# CHAIRI2CXIAO.net
KiCad netlist of a schematic drawn in EAGLE
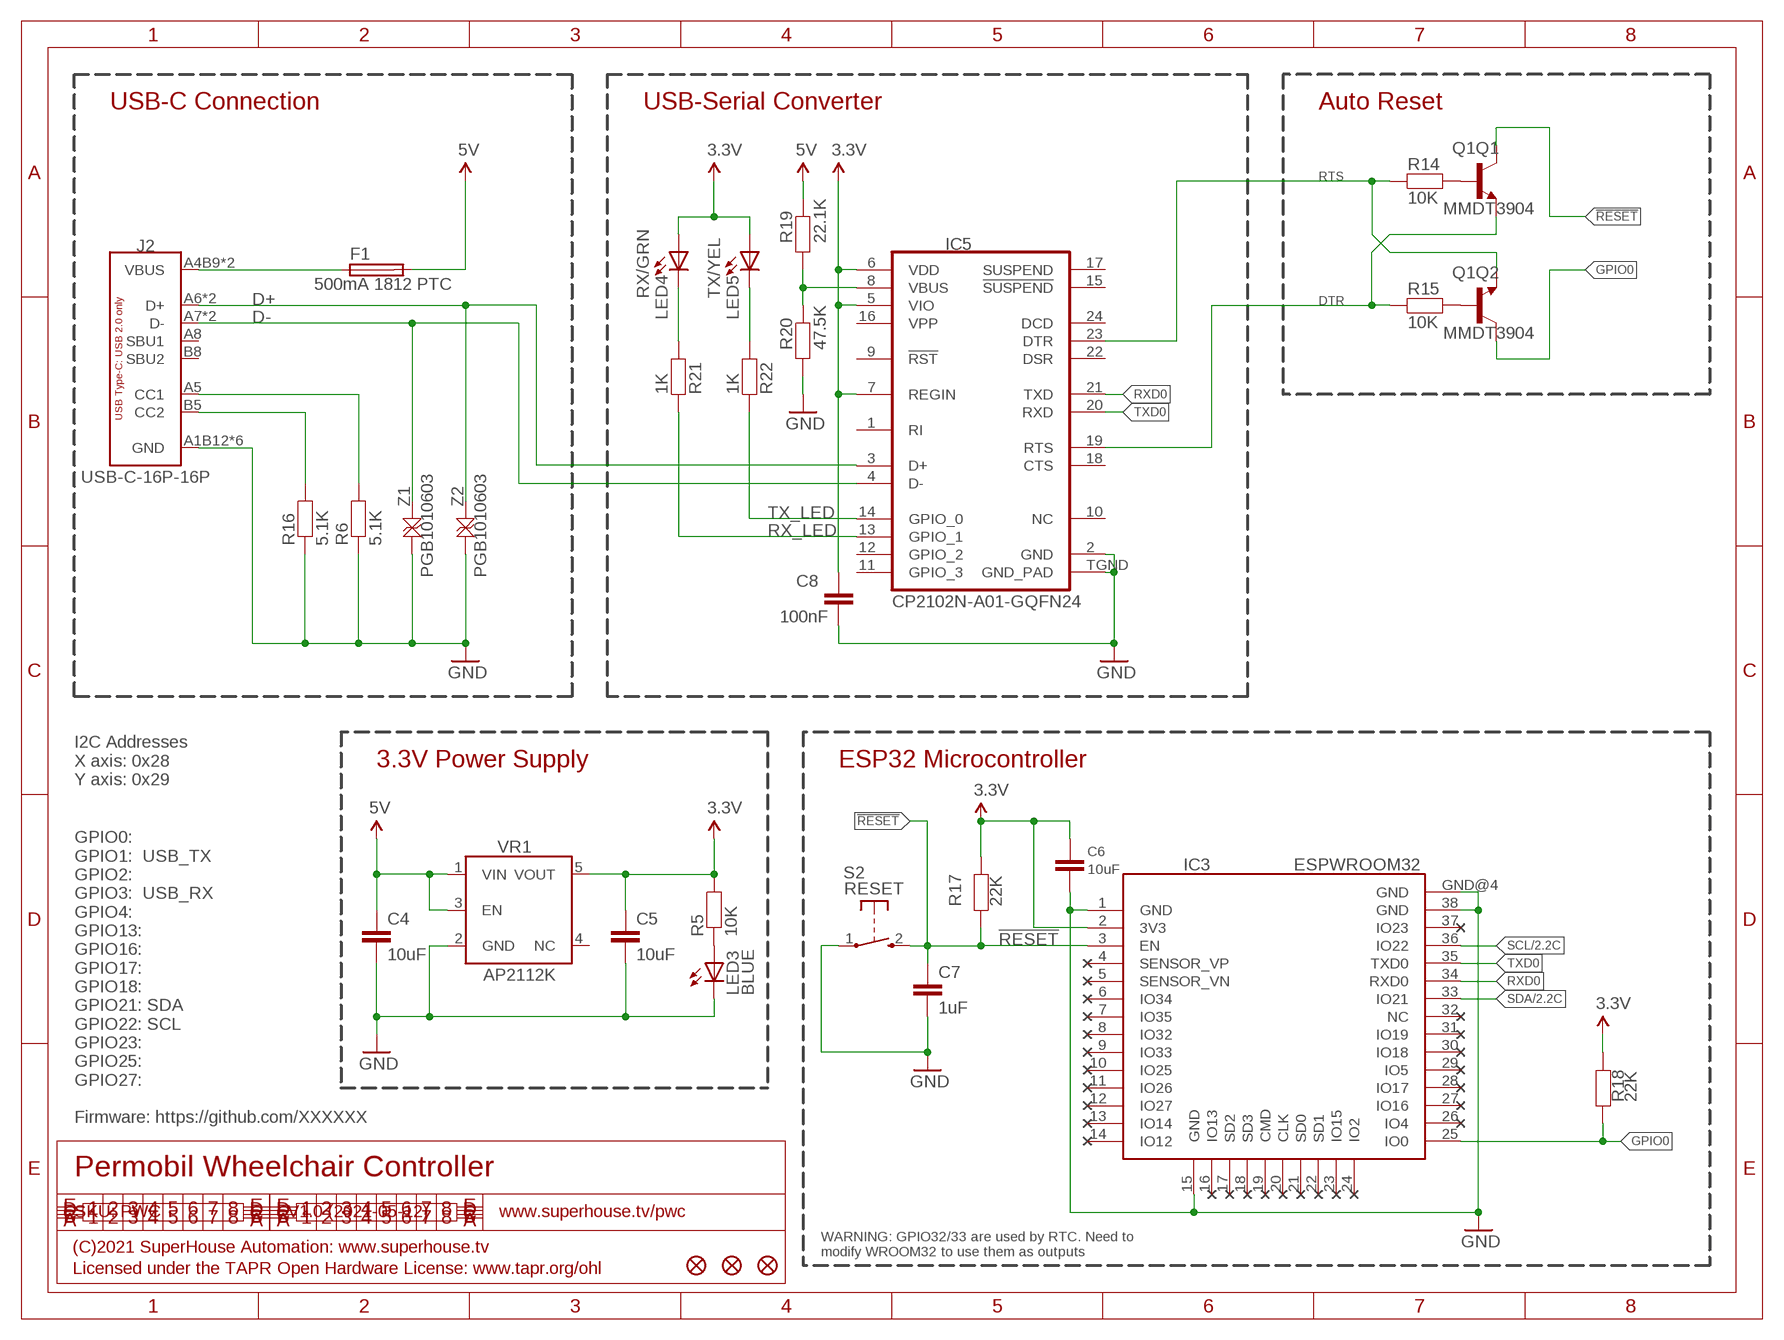
[diagram p0: schematic, sheet 1]
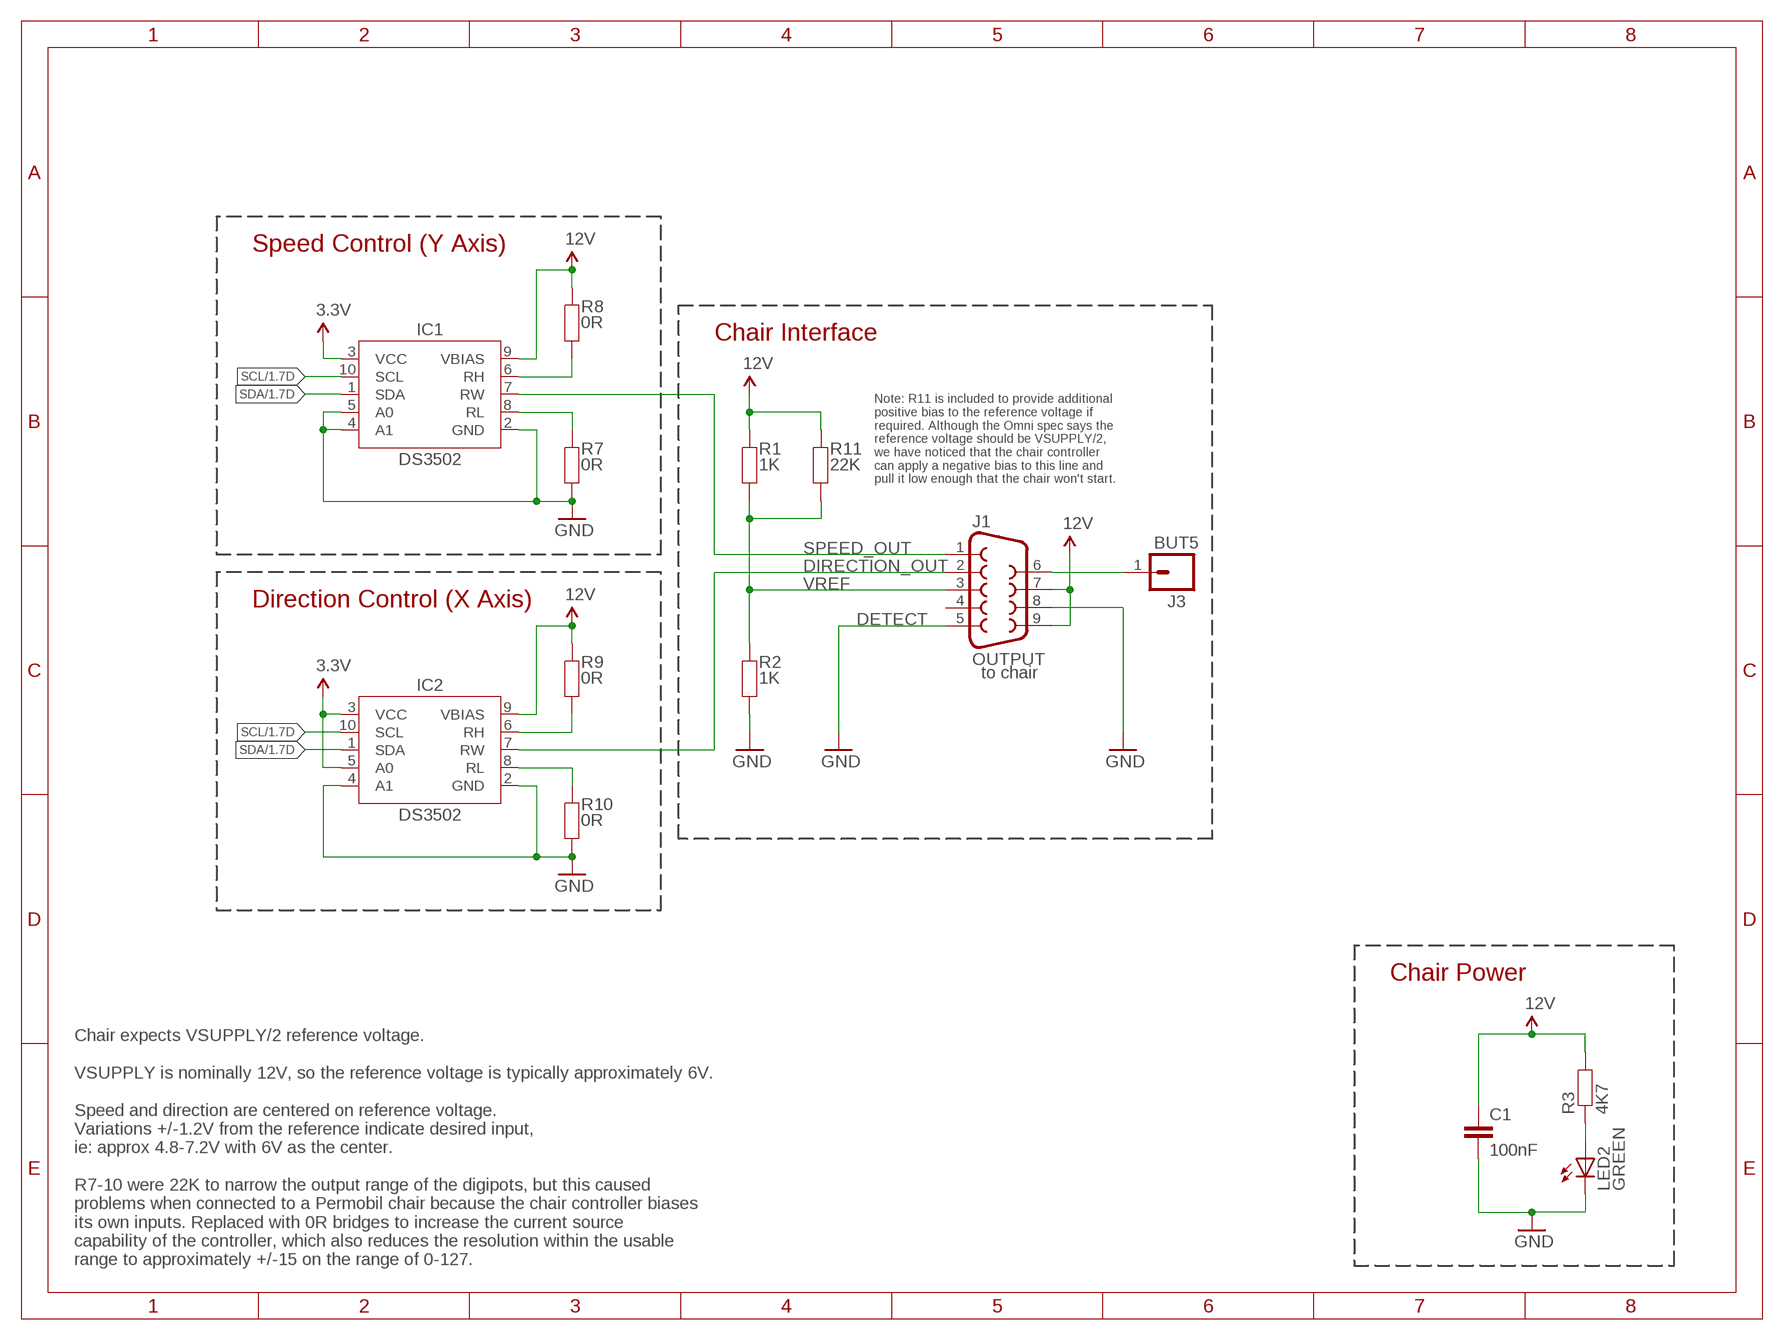
[diagram p1: schematic, sheet 2]

(export (version "E")
  (design (tool "Eeschema 10.0.6"))
  (components
    (comp (ref "C1")
      (value "100nF")
      (footprint "eagle-import:C0603")
      (libsource (lib "eagle-import") (part "CAP0603"))
    )
    (comp (ref "IC1")
      (value "DS3502")
      (footprint "eagle-import:MSOP10")
      (libsource (lib "eagle-import") (part "DS3502"))
    )
    (comp (ref "IC2")
      (value "DS3502")
      (footprint "eagle-import:MSOP10")
      (libsource (lib "eagle-import") (part "DS3502"))
    )
    (comp (ref "J1")
      (value "OUTPUT")
      (footprint "eagle-import:DB9-PCB-SOCKET")
      (libsource (lib "eagle-import") (part "DB9-PCB-SOCKET"))
    )
    (comp (ref "J3")
      (value "BUT5")
      (footprint "eagle-import:1X01")
      (libsource (lib "eagle-import") (part "M01-PLAIN"))
    )
    (comp (ref "LED2")
      (value "GREEN")
      (footprint "eagle-import:LED-0603")
      (libsource (lib "eagle-import") (part "LED0603"))
    )
    (comp (ref "R1")
      (value "1K")
      (footprint "eagle-import:R0603")
      (libsource (lib "eagle-import") (part "RESISTOR0603"))
    )
    (comp (ref "R2")
      (value "1K")
      (footprint "eagle-import:R0603")
      (libsource (lib "eagle-import") (part "RESISTOR0603"))
    )
    (comp (ref "R3")
      (value "4K7")
      (footprint "eagle-import:R0603")
      (libsource (lib "eagle-import") (part "RESISTOR0603"))
    )
    (comp (ref "R7")
      (value "0R")
      (footprint "eagle-import:R0603")
      (libsource (lib "eagle-import") (part "RESISTOR0603"))
    )
    (comp (ref "R8")
      (value "0R")
      (footprint "eagle-import:R0603")
      (libsource (lib "eagle-import") (part "RESISTOR0603"))
    )
    (comp (ref "R9")
      (value "0R")
      (footprint "eagle-import:R0603")
      (libsource (lib "eagle-import") (part "RESISTOR0603"))
    )
    (comp (ref "R10")
      (value "0R")
      (footprint "eagle-import:R0603")
      (libsource (lib "eagle-import") (part "RESISTOR0603"))
    )
    (comp (ref "R11")
      (value "22K")
      (footprint "eagle-import:R0603")
      (libsource (lib "eagle-import") (part "RESISTOR0603"))
    )
    (comp (ref "C4")
      (value "10uF")
      (footprint "eagle-import:C0805")
      (libsource (lib "eagle-import") (part "CAP0805"))
    )
    (comp (ref "C5")
      (value "10uF")
      (footprint "eagle-import:C0805")
      (libsource (lib "eagle-import") (part "CAP0805"))
    )
    (comp (ref "C6")
      (value "10uF")
      (footprint "eagle-import:C0805")
      (libsource (lib "eagle-import") (part "CAP0805"))
    )
    (comp (ref "C7")
      (value "1uF")
      (footprint "eagle-import:C0603")
      (libsource (lib "eagle-import") (part "CAP0603"))
    )
    (comp (ref "C8")
      (value "100nF")
      (footprint "eagle-import:C0603")
      (libsource (lib "eagle-import") (part "CAP0603"))
    )
    (comp (ref "F1")
      (value "500mA 1812 PTC")
      (footprint "eagle-import:1812")
      (libsource (lib "eagle-import") (part "PTC050"))
    )
    (comp (ref "IC3")
      (value "ESPWROOM32")
      (footprint "eagle-import:ESPWROOM32")
      (libsource (lib "eagle-import") (part "ESPWROOM32"))
    )
    (comp (ref "IC5")
      (value "CP2102N-A01-GQFN24")
      (footprint "eagle-import:QFN-24")
      (libsource (lib "eagle-import") (part "CP2104"))
    )
    (comp (ref "J2")
      (value "USB-C-16P-16P")
      (footprint "eagle-import:USB-C-16P")
      (libsource (lib "eagle-import") (part "USB-C-16P-16P"))
    )
    (comp (ref "LED3")
      (value "BLUE")
      (footprint "eagle-import:LED-0603")
      (libsource (lib "eagle-import") (part "LED0603"))
    )
    (comp (ref "LED4")
      (value "RX/GRN")
      (footprint "eagle-import:LED-0603")
      (libsource (lib "eagle-import") (part "LED0603"))
    )
    (comp (ref "LED5")
      (value "TX/YEL")
      (footprint "eagle-import:LED-0603")
      (libsource (lib "eagle-import") (part "LED0603"))
    )
    (comp (ref "Q1")
      (value "MMDT3904")
      (footprint "eagle-import:SOT-363")
      (libsource (lib "eagle-import") (part "TRANS_NPN_DUAL-MMDT3904"))
    )
    (comp (ref "R5")
      (value "10K")
      (footprint "eagle-import:R0603")
      (libsource (lib "eagle-import") (part "RESISTOR0603"))
    )
    (comp (ref "R6")
      (value "5.1K")
      (footprint "eagle-import:R0603")
      (libsource (lib "eagle-import") (part "RESISTOR0603"))
    )
    (comp (ref "R14")
      (value "10K")
      (footprint "eagle-import:R0603")
      (libsource (lib "eagle-import") (part "RESISTOR0603"))
    )
    (comp (ref "R15")
      (value "10K")
      (footprint "eagle-import:R0603")
      (libsource (lib "eagle-import") (part "RESISTOR0603"))
    )
    (comp (ref "R16")
      (value "5.1K")
      (footprint "eagle-import:R0603")
      (libsource (lib "eagle-import") (part "RESISTOR0603"))
    )
    (comp (ref "R17")
      (value "22K")
      (footprint "eagle-import:R0603")
      (libsource (lib "eagle-import") (part "RESISTOR0603"))
    )
    (comp (ref "R18")
      (value "22K")
      (footprint "eagle-import:R0603")
      (libsource (lib "eagle-import") (part "RESISTOR0603"))
    )
    (comp (ref "R19")
      (value "22.1K")
      (footprint "eagle-import:R0603")
      (libsource (lib "eagle-import") (part "RESISTOR0603"))
    )
    (comp (ref "R20")
      (value "47.5K")
      (footprint "eagle-import:R0603")
      (libsource (lib "eagle-import") (part "RESISTOR0603"))
    )
    (comp (ref "R21")
      (value "1K")
      (footprint "eagle-import:R0603")
      (libsource (lib "eagle-import") (part "RESISTOR0603"))
    )
    (comp (ref "R22")
      (value "1K")
      (footprint "eagle-import:R0603")
      (libsource (lib "eagle-import") (part "RESISTOR0603"))
    )
    (comp (ref "S2")
      (value "RESET")
      (footprint "eagle-import:TACTILE_SMT_3X4X2")
      (libsource (lib "eagle-import") (part "TAC_SWITCH_2PINSMT"))
    )
    (comp (ref "U$35")
      (value "FIDUCIAL1X2")
      (footprint "eagle-import:FIDUCIAL-1X2")
      (libsource (lib "eagle-import") (part "FIDUCIAL1X2"))
    )
    (comp (ref "U$36")
      (value "FIDUCIAL1X2")
      (footprint "eagle-import:FIDUCIAL-1X2")
      (libsource (lib "eagle-import") (part "FIDUCIAL1X2"))
    )
    (comp (ref "U$37")
      (value "FIDUCIAL1X2")
      (footprint "eagle-import:FIDUCIAL-1X2")
      (libsource (lib "eagle-import") (part "FIDUCIAL1X2"))
    )
    (comp (ref "VR1")
      (value "AP2112KSOT25")
      (footprint "eagle-import:SOT23-5")
      (libsource (lib "eagle-import") (part "AP2112KSOT25"))
    )
    (comp (ref "Z1")
      (value "PGB1010603")
      (footprint "eagle-import:TVS0603")
      (libsource (lib "eagle-import") (part "TVS0603"))
    )
    (comp (ref "Z2")
      (value "PGB1010603")
      (footprint "eagle-import:TVS0603")
      (libsource (lib "eagle-import") (part "TVS0603"))
    )
  )
  (nets
    (net (code "1") (name "3.3V") (class "Default")
      (node (ref "C5") (pin "1") (pinfunction "1_1") (pintype "passive"))
      (node (ref "C6") (pin "1") (pinfunction "1_1") (pintype "passive"))
      (node (ref "C8") (pin "1") (pinfunction "1_1") (pintype "passive"))
      (node (ref "IC1") (pin "3") (pinfunction "VCC_3") (pintype "power_in"))
      (node (ref "IC2") (pin "3") (pinfunction "VCC_3") (pintype "power_in"))
      (node (ref "IC2") (pin "5") (pinfunction "A0_5") (pintype "input"))
      (node (ref "IC3") (pin "2") (pinfunction "3V3_2") (pintype "power_in"))
      (node (ref "IC5") (pin "5") (pinfunction "VIO_5") (pintype "bidirectional"))
      (node (ref "IC5") (pin "6") (pinfunction "VDD_6") (pintype "power_in"))
      (node (ref "IC5") (pin "7") (pinfunction "REGIN_7") (pintype "power_in"))
      (node (ref "LED4") (pin "A") (pinfunction "A_A") (pintype "passive"))
      (node (ref "LED5") (pin "A") (pinfunction "A_A") (pintype "passive"))
      (node (ref "R17") (pin "1") (pinfunction "1_1") (pintype "passive"))
      (node (ref "R18") (pin "1") (pinfunction "1_1") (pintype "passive"))
      (node (ref "R5") (pin "2") (pinfunction "2_2") (pintype "passive"))
      (node (ref "VR1") (pin "5") (pinfunction "VOUT_5") (pintype "bidirectional"))
    )
    (net (code "2") (name "5V") (class "Default")
      (node (ref "C4") (pin "1") (pinfunction "1_1") (pintype "passive"))
      (node (ref "F1") (pin "2") (pinfunction "2_2") (pintype "passive"))
      (node (ref "R19") (pin "2") (pinfunction "2_2") (pintype "passive"))
      (node (ref "VR1") (pin "1") (pinfunction "VIN_1") (pintype "bidirectional"))
      (node (ref "VR1") (pin "3") (pinfunction "EN_3") (pintype "bidirectional"))
    )
    (net (code "3") (name "12V") (class "Default")
      (node (ref "C1") (pin "1") (pinfunction "1_1") (pintype "passive"))
      (node (ref "IC1") (pin "9") (pinfunction "VBIAS_9") (pintype "power_in"))
      (node (ref "IC2") (pin "9") (pinfunction "VBIAS_9") (pintype "power_in"))
      (node (ref "J1") (pin "7") (pinfunction "7_7") (pintype "passive"))
      (node (ref "J1") (pin "9") (pinfunction "9_9") (pintype "passive"))
      (node (ref "R1") (pin "2") (pinfunction "2_2") (pintype "passive"))
      (node (ref "R11") (pin "2") (pinfunction "2_2") (pintype "passive"))
      (node (ref "R3") (pin "2") (pinfunction "2_2") (pintype "passive"))
      (node (ref "R8") (pin "2") (pinfunction "2_2") (pintype "passive"))
      (node (ref "R9") (pin "2") (pinfunction "2_2") (pintype "passive"))
    )
    (net (code "4") (name "D+") (class "Default")
      (node (ref "IC5") (pin "3") (pinfunction "D+_3") (pintype "bidirectional"))
      (node (ref "J2") (pin "A6") (pinfunction "D+_A6") (pintype "bidirectional"))
      (node (ref "J2") (pin "B6") (pinfunction "D+_B6") (pintype "bidirectional"))
      (node (ref "Z2") (pin "2") (pinfunction "2_2") (pintype "passive"))
    )
    (net (code "5") (name "D-") (class "Default")
      (node (ref "IC5") (pin "4") (pinfunction "D-_4") (pintype "bidirectional"))
      (node (ref "J2") (pin "A7") (pinfunction "D-_A7") (pintype "bidirectional"))
      (node (ref "J2") (pin "B7") (pinfunction "D-_B7") (pintype "bidirectional"))
      (node (ref "Z1") (pin "2") (pinfunction "2_2") (pintype "passive"))
    )
    (net (code "6") (name "DIRECTION_OUT") (class "Default")
      (node (ref "IC2") (pin "7") (pinfunction "RW_7") (pintype "passive"))
      (node (ref "J1") (pin "2") (pinfunction "2_2") (pintype "passive"))
    )
    (net (code "7") (name "DTR") (class "Default")
      (node (ref "IC5") (pin "23") (pinfunction "DTR_23") (pintype "output"))
      (node (ref "Q1") (pin "1") (pinfunction "E_1") (pintype "passive"))
      (node (ref "R14") (pin "1") (pinfunction "1_1") (pintype "passive"))
    )
    (net (code "8") (name "GND") (class "Default")
      (node (ref "C1") (pin "2") (pinfunction "2_2") (pintype "passive"))
      (node (ref "C4") (pin "2") (pinfunction "2_2") (pintype "passive"))
      (node (ref "C5") (pin "2") (pinfunction "2_2") (pintype "passive"))
      (node (ref "C6") (pin "2") (pinfunction "2_2") (pintype "passive"))
      (node (ref "C7") (pin "2") (pinfunction "2_2") (pintype "passive"))
      (node (ref "C8") (pin "2") (pinfunction "2_2") (pintype "passive"))
      (node (ref "IC1") (pin "2") (pinfunction "GND_2") (pintype "power_in"))
      (node (ref "IC1") (pin "4") (pinfunction "A1_4") (pintype "input"))
      (node (ref "IC1") (pin "5") (pinfunction "A0_5") (pintype "input"))
      (node (ref "IC2") (pin "2") (pinfunction "GND_2") (pintype "power_in"))
      (node (ref "IC2") (pin "4") (pinfunction "A1_4") (pintype "input"))
      (node (ref "IC3") (pin "1") (pinfunction "GND_1") (pintype "power_in"))
      (node (ref "IC3") (pin "15") (pinfunction "GND_15") (pintype "power_in"))
      (node (ref "IC3") (pin "38") (pinfunction "GND_38") (pintype "power_in"))
      (node (ref "IC3") (pin "GND@4") (pinfunction "GND_GND@4") (pintype "power_in"))
      (node (ref "IC5") (pin "2") (pinfunction "GND_2") (pintype "power_in"))
      (node (ref "IC5") (pin "TGND") (pinfunction "GND_PAD_TGND") (pintype "power_in"))
      (node (ref "J1") (pin "5") (pinfunction "5_5") (pintype "passive"))
      (node (ref "J1") (pin "8") (pinfunction "8_8") (pintype "passive"))
      (node (ref "J2") (pin "A12B1") (pinfunction "GND_A12B1") (pintype "power_in"))
      (node (ref "J2") (pin "A1B12") (pinfunction "GND_A1B12") (pintype "power_in"))
      (node (ref "J2") (pin "FIX1") (pinfunction "GND_FIX1") (pintype "power_in"))
      (node (ref "J2") (pin "FIX2") (pinfunction "GND_FIX2") (pintype "power_in"))
      (node (ref "J2") (pin "FIX3") (pinfunction "GND_FIX3") (pintype "power_in"))
      (node (ref "J2") (pin "FIX4") (pinfunction "GND_FIX4") (pintype "power_in"))
      (node (ref "LED2") (pin "C") (pinfunction "C_C") (pintype "passive"))
      (node (ref "LED3") (pin "C") (pinfunction "C_C") (pintype "passive"))
      (node (ref "R10") (pin "1") (pinfunction "1_1") (pintype "passive"))
      (node (ref "R16") (pin "1") (pinfunction "1_1") (pintype "passive"))
      (node (ref "R2") (pin "1") (pinfunction "1_1") (pintype "passive"))
      (node (ref "R20") (pin "1") (pinfunction "1_1") (pintype "passive"))
      (node (ref "R6") (pin "1") (pinfunction "1_1") (pintype "passive"))
      (node (ref "R7") (pin "1") (pinfunction "1_1") (pintype "passive"))
      (node (ref "S2") (pin "1") (pinfunction "P_1") (pintype "passive"))
      (node (ref "VR1") (pin "2") (pinfunction "GND_2") (pintype "bidirectional"))
      (node (ref "Z1") (pin "1") (pinfunction "1_1") (pintype "passive"))
      (node (ref "Z2") (pin "1") (pinfunction "1_1") (pintype "passive"))
    )
    (net (code "9") (name "GPIO0") (class "Default")
      (node (ref "IC3") (pin "25") (pinfunction "IO0_25") (pintype "bidirectional"))
      (node (ref "Q1") (pin "6") (pinfunction "C_6") (pintype "passive"))
      (node (ref "R18") (pin "2") (pinfunction "2_2") (pintype "passive"))
    )
    (net (code "10") (name "Net-(F1-Pad1)") (class "Default")
      (node (ref "F1") (pin "1") (pinfunction "1_1") (pintype "passive"))
      (node (ref "J2") (pin "A4B9") (pinfunction "VBUS_A4B9") (pintype "power_in"))
      (node (ref "J2") (pin "A9B4") (pinfunction "VBUS_A9B4") (pintype "power_in"))
    )
    (net (code "11") (name "Net-(IC1-RH)") (class "Default")
      (node (ref "IC1") (pin "6") (pinfunction "RH_6") (pintype "passive"))
      (node (ref "R8") (pin "1") (pinfunction "1_1") (pintype "passive"))
    )
    (net (code "12") (name "Net-(IC1-RL)") (class "Default")
      (node (ref "IC1") (pin "8") (pinfunction "RL_8") (pintype "passive"))
      (node (ref "R7") (pin "2") (pinfunction "2_2") (pintype "passive"))
    )
    (net (code "13") (name "Net-(IC2-RH)") (class "Default")
      (node (ref "IC2") (pin "6") (pinfunction "RH_6") (pintype "passive"))
      (node (ref "R9") (pin "1") (pinfunction "1_1") (pintype "passive"))
    )
    (net (code "14") (name "Net-(IC2-RL)") (class "Default")
      (node (ref "IC2") (pin "8") (pinfunction "RL_8") (pintype "passive"))
      (node (ref "R10") (pin "2") (pinfunction "2_2") (pintype "passive"))
    )
    (net (code "15") (name "Net-(IC5-VBUS)") (class "Default")
      (node (ref "IC5") (pin "8") (pinfunction "VBUS_8") (pintype "bidirectional"))
      (node (ref "R19") (pin "1") (pinfunction "1_1") (pintype "passive"))
      (node (ref "R20") (pin "2") (pinfunction "2_2") (pintype "passive"))
    )
    (net (code "16") (name "Net-(J1-Pad6)") (class "Default")
      (node (ref "J1") (pin "6") (pinfunction "6_6") (pintype "passive"))
      (node (ref "J3") (pin "1") (pinfunction "1_1") (pintype "passive"))
    )
    (net (code "17") (name "Net-(J2-CC1)") (class "Default")
      (node (ref "J2") (pin "A5") (pinfunction "CC1_A5") (pintype "bidirectional"))
      (node (ref "R6") (pin "2") (pinfunction "2_2") (pintype "passive"))
    )
    (net (code "18") (name "Net-(J2-CC2)") (class "Default")
      (node (ref "J2") (pin "B5") (pinfunction "CC2_B5") (pintype "bidirectional"))
      (node (ref "R16") (pin "2") (pinfunction "2_2") (pintype "passive"))
    )
    (net (code "19") (name "Net-(LED2-PadA)") (class "Default")
      (node (ref "LED2") (pin "A") (pinfunction "A_A") (pintype "passive"))
      (node (ref "R3") (pin "1") (pinfunction "1_1") (pintype "passive"))
    )
    (net (code "20") (name "Net-(LED3-PadA)") (class "Default")
      (node (ref "LED3") (pin "A") (pinfunction "A_A") (pintype "passive"))
      (node (ref "R5") (pin "1") (pinfunction "1_1") (pintype "passive"))
    )
    (net (code "21") (name "Net-(LED4-PadC)") (class "Default")
      (node (ref "LED4") (pin "C") (pinfunction "C_C") (pintype "passive"))
      (node (ref "R21") (pin "2") (pinfunction "2_2") (pintype "passive"))
    )
    (net (code "22") (name "Net-(LED5-PadC)") (class "Default")
      (node (ref "LED5") (pin "C") (pinfunction "C_C") (pintype "passive"))
      (node (ref "R22") (pin "2") (pinfunction "2_2") (pintype "passive"))
    )
    (net (code "23") (name "Net-(Q1A-B)") (class "Default")
      (node (ref "Q1") (pin "5") (pinfunction "B_5") (pintype "passive"))
      (node (ref "R14") (pin "2") (pinfunction "2_2") (pintype "passive"))
    )
    (net (code "24") (name "Net-(Q1B-B)") (class "Default")
      (node (ref "Q1") (pin "2") (pinfunction "B_2") (pintype "passive"))
      (node (ref "R15") (pin "2") (pinfunction "2_2") (pintype "passive"))
    )
    (net (code "25") (name "RTS") (class "Default")
      (node (ref "IC5") (pin "19") (pinfunction "RTS_19") (pintype "output"))
      (node (ref "Q1") (pin "4") (pinfunction "E_4") (pintype "passive"))
      (node (ref "R15") (pin "1") (pinfunction "1_1") (pintype "passive"))
    )
    (net (code "26") (name "RXD0") (class "Default")
      (node (ref "IC3") (pin "34") (pinfunction "RXD0_34") (pintype "bidirectional"))
      (node (ref "IC5") (pin "21") (pinfunction "TXD_21") (pintype "output"))
    )
    (net (code "27") (name "RX_LED") (class "Default")
      (node (ref "IC5") (pin "13") (pinfunction "GPIO_1_13") (pintype "bidirectional"))
      (node (ref "R21") (pin "1") (pinfunction "1_1") (pintype "passive"))
    )
    (net (code "28") (name "SCL") (class "Default")
      (node (ref "IC1") (pin "10") (pinfunction "SCL_10") (pintype "input"))
      (node (ref "IC2") (pin "10") (pinfunction "SCL_10") (pintype "input"))
      (node (ref "IC3") (pin "36") (pinfunction "IO22_36") (pintype "bidirectional"))
    )
    (net (code "29") (name "SDA") (class "Default")
      (node (ref "IC1") (pin "1") (pinfunction "SDA_1") (pintype "bidirectional"))
      (node (ref "IC2") (pin "1") (pinfunction "SDA_1") (pintype "bidirectional"))
      (node (ref "IC3") (pin "33") (pinfunction "IO21_33") (pintype "bidirectional"))
    )
    (net (code "30") (name "SPEED_OUT") (class "Default")
      (node (ref "IC1") (pin "7") (pinfunction "RW_7") (pintype "passive"))
      (node (ref "J1") (pin "1") (pinfunction "1_1") (pintype "passive"))
    )
    (net (code "31") (name "TXD0") (class "Default")
      (node (ref "IC3") (pin "35") (pinfunction "TXD0_35") (pintype "bidirectional"))
      (node (ref "IC5") (pin "20") (pinfunction "RXD_20") (pintype "input"))
    )
    (net (code "32") (name "TX_LED") (class "Default")
      (node (ref "IC5") (pin "14") (pinfunction "GPIO_0_14") (pintype "bidirectional"))
      (node (ref "R22") (pin "1") (pinfunction "1_1") (pintype "passive"))
    )
    (net (code "33") (name "VREF") (class "Default")
      (node (ref "J1") (pin "3") (pinfunction "3_3") (pintype "passive"))
      (node (ref "R1") (pin "1") (pinfunction "1_1") (pintype "passive"))
      (node (ref "R11") (pin "1") (pinfunction "1_1") (pintype "passive"))
      (node (ref "R2") (pin "2") (pinfunction "2_2") (pintype "passive"))
    )
    (net (code "34") (name "unconnected-(IC3-CLK-Pad20)") (class "Default")
      (node (ref "IC3") (pin "20") (pinfunction "CLK_20") (pintype "bidirectional"))
    )
    (net (code "35") (name "unconnected-(IC3-CMD-Pad19)") (class "Default")
      (node (ref "IC3") (pin "19") (pinfunction "CMD_19") (pintype "bidirectional"))
    )
    (net (code "36") (name "unconnected-(IC3-IO2-Pad24)") (class "Default")
      (node (ref "IC3") (pin "24") (pinfunction "IO2_24") (pintype "bidirectional"))
    )
    (net (code "37") (name "unconnected-(IC3-IO4-Pad26)") (class "Default")
      (node (ref "IC3") (pin "26") (pinfunction "IO4_26") (pintype "bidirectional"))
    )
    (net (code "38") (name "unconnected-(IC3-IO5-Pad29)") (class "Default")
      (node (ref "IC3") (pin "29") (pinfunction "IO5_29") (pintype "bidirectional"))
    )
    (net (code "39") (name "unconnected-(IC3-IO12-Pad14)") (class "Default")
      (node (ref "IC3") (pin "14") (pinfunction "IO12_14") (pintype "bidirectional"))
    )
    (net (code "40") (name "unconnected-(IC3-IO13-Pad16)") (class "Default")
      (node (ref "IC3") (pin "16") (pinfunction "IO13_16") (pintype "bidirectional"))
    )
    (net (code "41") (name "unconnected-(IC3-IO14-Pad13)") (class "Default")
      (node (ref "IC3") (pin "13") (pinfunction "IO14_13") (pintype "bidirectional"))
    )
    (net (code "42") (name "unconnected-(IC3-IO15-Pad23)") (class "Default")
      (node (ref "IC3") (pin "23") (pinfunction "IO15_23") (pintype "bidirectional"))
    )
    (net (code "43") (name "unconnected-(IC3-IO16-Pad27)") (class "Default")
      (node (ref "IC3") (pin "27") (pinfunction "IO16_27") (pintype "bidirectional"))
    )
    (net (code "44") (name "unconnected-(IC3-IO17-Pad28)") (class "Default")
      (node (ref "IC3") (pin "28") (pinfunction "IO17_28") (pintype "bidirectional"))
    )
    (net (code "45") (name "unconnected-(IC3-IO18-Pad30)") (class "Default")
      (node (ref "IC3") (pin "30") (pinfunction "IO18_30") (pintype "bidirectional"))
    )
    (net (code "46") (name "unconnected-(IC3-IO19-Pad31)") (class "Default")
      (node (ref "IC3") (pin "31") (pinfunction "IO19_31") (pintype "bidirectional"))
    )
    (net (code "47") (name "unconnected-(IC3-IO23-Pad37)") (class "Default")
      (node (ref "IC3") (pin "37") (pinfunction "IO23_37") (pintype "bidirectional"))
    )
    (net (code "48") (name "unconnected-(IC3-IO25-Pad10)") (class "Default")
      (node (ref "IC3") (pin "10") (pinfunction "IO25_10") (pintype "bidirectional"))
    )
    (net (code "49") (name "unconnected-(IC3-IO26-Pad11)") (class "Default")
      (node (ref "IC3") (pin "11") (pinfunction "IO26_11") (pintype "bidirectional"))
    )
    (net (code "50") (name "unconnected-(IC3-IO27-Pad12)") (class "Default")
      (node (ref "IC3") (pin "12") (pinfunction "IO27_12") (pintype "bidirectional"))
    )
    (net (code "51") (name "unconnected-(IC3-IO32-Pad8)") (class "Default")
      (node (ref "IC3") (pin "8") (pinfunction "IO32_8") (pintype "bidirectional"))
    )
    (net (code "52") (name "unconnected-(IC3-IO33-Pad9)") (class "Default")
      (node (ref "IC3") (pin "9") (pinfunction "IO33_9") (pintype "bidirectional"))
    )
    (net (code "53") (name "unconnected-(IC3-IO34-Pad6)") (class "Default")
      (node (ref "IC3") (pin "6") (pinfunction "IO34_6") (pintype "bidirectional"))
    )
    (net (code "54") (name "unconnected-(IC3-IO35-Pad7)") (class "Default")
      (node (ref "IC3") (pin "7") (pinfunction "IO35_7") (pintype "bidirectional"))
    )
    (net (code "55") (name "unconnected-(IC3-NC-Pad32)") (class "Default")
      (node (ref "IC3") (pin "32") (pinfunction "NC_32") (pintype "bidirectional"))
    )
    (net (code "56") (name "unconnected-(IC3-SD0-Pad21)") (class "Default")
      (node (ref "IC3") (pin "21") (pinfunction "SD0_21") (pintype "bidirectional"))
    )
    (net (code "57") (name "unconnected-(IC3-SD1-Pad22)") (class "Default")
      (node (ref "IC3") (pin "22") (pinfunction "SD1_22") (pintype "bidirectional"))
    )
    (net (code "58") (name "unconnected-(IC3-SD2-Pad17)") (class "Default")
      (node (ref "IC3") (pin "17") (pinfunction "SD2_17") (pintype "bidirectional"))
    )
    (net (code "59") (name "unconnected-(IC3-SD3-Pad18)") (class "Default")
      (node (ref "IC3") (pin "18") (pinfunction "SD3_18") (pintype "bidirectional"))
    )
    (net (code "60") (name "unconnected-(IC3-SENSOR_VN-Pad5)") (class "Default")
      (node (ref "IC3") (pin "5") (pinfunction "SENSOR_VN_5") (pintype "bidirectional"))
    )
    (net (code "61") (name "unconnected-(IC3-SENSOR_VP-Pad4)") (class "Default")
      (node (ref "IC3") (pin "4") (pinfunction "SENSOR_VP_4") (pintype "bidirectional"))
    )
    (net (code "62") (name "unconnected-(IC5-CTS-Pad18)") (class "Default")
      (node (ref "IC5") (pin "18") (pinfunction "CTS_18") (pintype "input"))
    )
    (net (code "63") (name "unconnected-(IC5-DCD-Pad24)") (class "Default")
      (node (ref "IC5") (pin "24") (pinfunction "DCD_24") (pintype "input"))
    )
    (net (code "64") (name "unconnected-(IC5-DSR-Pad22)") (class "Default")
      (node (ref "IC5") (pin "22") (pinfunction "DSR_22") (pintype "input"))
    )
    (net (code "65") (name "unconnected-(IC5-GPIO_2-Pad12)") (class "Default")
      (node (ref "IC5") (pin "12") (pinfunction "GPIO_2_12") (pintype "bidirectional"))
    )
    (net (code "66") (name "unconnected-(IC5-GPIO_3-Pad11)") (class "Default")
      (node (ref "IC5") (pin "11") (pinfunction "GPIO_3_11") (pintype "bidirectional"))
    )
    (net (code "67") (name "unconnected-(IC5-NC-Pad10)") (class "Default")
      (node (ref "IC5") (pin "10") (pinfunction "NC_10") (pintype "input"))
    )
    (net (code "68") (name "unconnected-(IC5-RI-Pad1)") (class "Default")
      (node (ref "IC5") (pin "1") (pinfunction "RI_1") (pintype "input"))
    )
    (net (code "69") (name "unconnected-(IC5-SUSPEND-Pad17)") (class "Default")
      (node (ref "IC5") (pin "17") (pinfunction "SUSPEND_17") (pintype "output"))
    )
    (net (code "70") (name "unconnected-(IC5-VPP-Pad16)") (class "Default")
      (node (ref "IC5") (pin "16") (pinfunction "VPP_16") (pintype "bidirectional"))
    )
    (net (code "71") (name "unconnected-(IC5-~{RST}-Pad9)") (class "Default")
      (node (ref "IC5") (pin "9") (pinfunction "~{RST}_9") (pintype "bidirectional"))
    )
    (net (code "72") (name "unconnected-(IC5-~{SUSPEND}-Pad15)") (class "Default")
      (node (ref "IC5") (pin "15") (pinfunction "~{SUSPEND}_15") (pintype "output"))
    )
    (net (code "73") (name "unconnected-(J1-Pad4)") (class "Default")
      (node (ref "J1") (pin "4") (pinfunction "4_4") (pintype "passive"))
    )
    (net (code "74") (name "unconnected-(J2-SBU1-PadA8)") (class "Default")
      (node (ref "J2") (pin "A8") (pinfunction "SBU1_A8") (pintype "bidirectional"))
    )
    (net (code "75") (name "unconnected-(J2-SBU2-PadB8)") (class "Default")
      (node (ref "J2") (pin "B8") (pinfunction "SBU2_B8") (pintype "bidirectional"))
    )
    (net (code "76") (name "unconnected-(VR1-NC-Pad4)") (class "Default")
      (node (ref "VR1") (pin "4") (pinfunction "NC_4") (pintype "bidirectional"))
    )
    (net (code "77") (name "~{RESET}") (class "Default")
      (node (ref "C7") (pin "1") (pinfunction "1_1") (pintype "passive"))
      (node (ref "IC3") (pin "3") (pinfunction "EN_3") (pintype "bidirectional"))
      (node (ref "Q1") (pin "3") (pinfunction "C_3") (pintype "passive"))
      (node (ref "R17") (pin "2") (pinfunction "2_2") (pintype "passive"))
      (node (ref "S2") (pin "2") (pinfunction "S_2") (pintype "passive"))
    )
  )
)
